# HDMI.net
KiCad netlist of a schematic drawn in Altium Designer
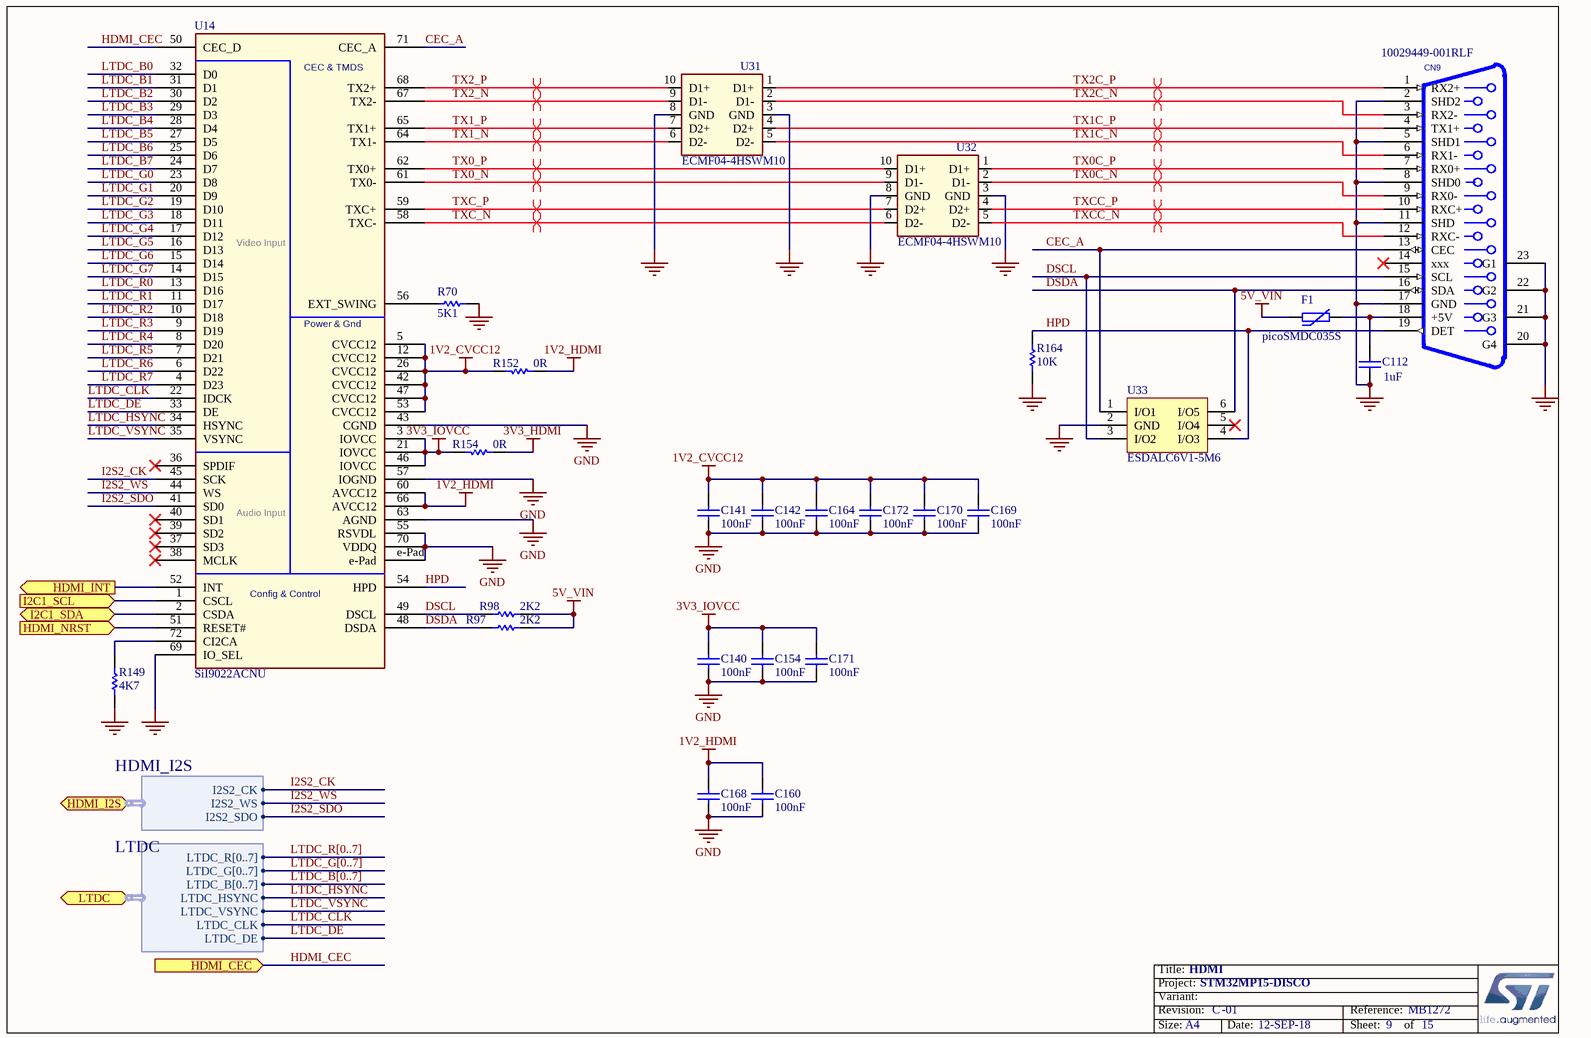
[diagram p0: HDMI.SchDoc]

(export (version "E")
  (design (tool "Eeschema 10.0.6"))
  (components
    (comp (ref "C112")
      (value "1uF")
      (footprint "C0402")
      (description "Capacitor,1uF,6V3,X5R,10%,0402")
      (fields
        (field (name "INTERNAL_PART_NUMBER") "MCD-00095")
        (field (name "MANUFACTURER_PART_NUMBER") "GRM155R61E105KA12")
        (field (name "PROVIDED_BY") "SUBCO")
      )
      (libsource (lib "MCD_PARTS_database") (part "Capacitor"))
    )
    (comp (ref "C140")
      (value "100nF")
      (footprint "C0402")
      (description "Capacitor,100nF,16V,X7R,10%,0402")
      (fields
        (field (name "INTERNAL_PART_NUMBER") "MCD-00006")
        (field (name "MANUFACTURER_PART_NUMBER") "CC0402KRX7R7BB104")
        (field (name "PROVIDED_BY") "SUBCO")
      )
      (libsource (lib "MCD_PARTS_database") (part "Capacitor"))
    )
    (comp (ref "C141")
      (value "100nF")
      (footprint "C0402")
      (description "Capacitor,100nF,16V,X7R,10%,0402")
      (fields
        (field (name "INTERNAL_PART_NUMBER") "MCD-00006")
        (field (name "MANUFACTURER_PART_NUMBER") "CC0402KRX7R7BB104")
        (field (name "PROVIDED_BY") "SUBCO")
      )
      (libsource (lib "MCD_PARTS_database") (part "Capacitor"))
    )
    (comp (ref "C142")
      (value "100nF")
      (footprint "C0402")
      (description "Capacitor,100nF,16V,X7R,10%,0402")
      (fields
        (field (name "INTERNAL_PART_NUMBER") "MCD-00006")
        (field (name "MANUFACTURER_PART_NUMBER") "CC0402KRX7R7BB104")
        (field (name "PROVIDED_BY") "SUBCO")
      )
      (libsource (lib "MCD_PARTS_database") (part "Capacitor"))
    )
    (comp (ref "C154")
      (value "100nF")
      (footprint "C0402")
      (description "Capacitor,100nF,16V,X7R,10%,0402")
      (fields
        (field (name "INTERNAL_PART_NUMBER") "MCD-00006")
        (field (name "MANUFACTURER_PART_NUMBER") "CC0402KRX7R7BB104")
        (field (name "PROVIDED_BY") "SUBCO")
      )
      (libsource (lib "MCD_PARTS_database") (part "Capacitor"))
    )
    (comp (ref "C160")
      (value "100nF")
      (footprint "C0402")
      (description "Capacitor,100nF,16V,X7R,10%,0402")
      (fields
        (field (name "INTERNAL_PART_NUMBER") "MCD-00006")
        (field (name "MANUFACTURER_PART_NUMBER") "CC0402KRX7R7BB104")
        (field (name "PROVIDED_BY") "SUBCO")
      )
      (libsource (lib "MCD_PARTS_database") (part "Capacitor"))
    )
    (comp (ref "C164")
      (value "100nF")
      (footprint "C0402")
      (description "Capacitor,100nF,16V,X7R,10%,0402")
      (fields
        (field (name "INTERNAL_PART_NUMBER") "MCD-00006")
        (field (name "MANUFACTURER_PART_NUMBER") "CC0402KRX7R7BB104")
        (field (name "PROVIDED_BY") "SUBCO")
      )
      (libsource (lib "MCD_PARTS_database") (part "Capacitor"))
    )
    (comp (ref "C168")
      (value "100nF")
      (footprint "C0402")
      (description "Capacitor,100nF,16V,X7R,10%,0402")
      (fields
        (field (name "INTERNAL_PART_NUMBER") "MCD-00006")
        (field (name "MANUFACTURER_PART_NUMBER") "CC0402KRX7R7BB104")
        (field (name "PROVIDED_BY") "SUBCO")
      )
      (libsource (lib "MCD_PARTS_database") (part "Capacitor"))
    )
    (comp (ref "C169")
      (value "100nF")
      (footprint "C0402")
      (description "Capacitor,100nF,16V,X7R,10%,0402")
      (fields
        (field (name "INTERNAL_PART_NUMBER") "MCD-00006")
        (field (name "MANUFACTURER_PART_NUMBER") "CC0402KRX7R7BB104")
        (field (name "PROVIDED_BY") "SUBCO")
      )
      (libsource (lib "MCD_PARTS_database") (part "Capacitor"))
    )
    (comp (ref "C170")
      (value "100nF")
      (footprint "C0402")
      (description "Capacitor,100nF,16V,X7R,10%,0402")
      (fields
        (field (name "INTERNAL_PART_NUMBER") "MCD-00006")
        (field (name "MANUFACTURER_PART_NUMBER") "CC0402KRX7R7BB104")
        (field (name "PROVIDED_BY") "SUBCO")
      )
      (libsource (lib "MCD_PARTS_database") (part "Capacitor"))
    )
    (comp (ref "C171")
      (value "100nF")
      (footprint "C0402")
      (description "Capacitor,100nF,16V,X7R,10%,0402")
      (fields
        (field (name "INTERNAL_PART_NUMBER") "MCD-00006")
        (field (name "MANUFACTURER_PART_NUMBER") "CC0402KRX7R7BB104")
        (field (name "PROVIDED_BY") "SUBCO")
      )
      (libsource (lib "MCD_PARTS_database") (part "Capacitor"))
    )
    (comp (ref "C172")
      (value "100nF")
      (footprint "C0402")
      (description "Capacitor,100nF,16V,X7R,10%,0402")
      (fields
        (field (name "INTERNAL_PART_NUMBER") "MCD-00006")
        (field (name "MANUFACTURER_PART_NUMBER") "CC0402KRX7R7BB104")
        (field (name "PROVIDED_BY") "SUBCO")
      )
      (libsource (lib "MCD_PARTS_database") (part "Capacitor"))
    )
    (comp (ref "CN9")
      (value "10029449-001RLF")
      (footprint "CON_HDMI_FCI-AMPHENOL_10029449-001RLF")
      (description "HDMI Receptacle Type A 19pins standard Connector")
      (fields
        (field (name "INTERNAL_PART_NUMBER") "MCD-00307")
        (field (name "MANUFACTURER") "FCI")
        (field (name "PROVIDED_BY") "SUBCO")
      )
      (libsource (lib "MCD_PARTS_database") (part "HDMI_TypeA_DB19_7"))
    )
    (comp (ref "F1")
      (value "picoSMDC035S")
      (footprint "R0805")
      (description "Surface mount resettable polyswitch fuse.I hold=0.35A and I trigger=0.75A")
      (fields
        (field (name "INTERNAL_PART_NUMBER") "MCD-01133")
        (field (name "MANUFACTURER") "TE CONNECTIVITY")
        (field (name "PROVIDED_BY") "SUBCO")
      )
      (libsource (lib "MCD_PARTS_database") (part "picoSMDC035S"))
    )
    (comp (ref "R70")
      (value "5K1")
      (footprint "R0402")
      (description "Resistor,5K1,0402,1%,1/16W")
      (fields
        (field (name "INTERNAL_PART_NUMBER") "MCD-00333")
        (field (name "MANUFACTURER_PART_NUMBER") "RC0402FR-075K1L")
        (field (name "PROVIDED_BY") "SUBCO")
      )
      (libsource (lib "MCD_PARTS_database") (part "Resistor"))
    )
    (comp (ref "R97")
      (value "2K2")
      (footprint "R0402")
      (description "Resistor,2K2,0402,1%,1/16W")
      (fields
        (field (name "INTERNAL_PART_NUMBER") "MCD-00057")
        (field (name "MANUFACTURER_PART_NUMBER") "RC0402FR-072K2L")
        (field (name "PROVIDED_BY") "SUBCO")
      )
      (libsource (lib "MCD_PARTS_database") (part "Resistor"))
    )
    (comp (ref "R98")
      (value "2K2")
      (footprint "R0402")
      (description "Resistor,2K2,0402,1%,1/16W")
      (fields
        (field (name "INTERNAL_PART_NUMBER") "MCD-00057")
        (field (name "MANUFACTURER_PART_NUMBER") "RC0402FR-072K2L")
        (field (name "PROVIDED_BY") "SUBCO")
      )
      (libsource (lib "MCD_PARTS_database") (part "Resistor"))
    )
    (comp (ref "R149")
      (value "4K7")
      (footprint "R0402")
      (description "Resistor,4K7,0402,1%,1/16W")
      (fields
        (field (name "INTERNAL_PART_NUMBER") "MCD-00065")
        (field (name "MANUFACTURER_PART_NUMBER") "RC0402FR-074K7L")
        (field (name "PROVIDED_BY") "SUBCO")
      )
      (libsource (lib "MCD_PARTS_database") (part "Resistor"))
    )
    (comp (ref "R152")
      (value "0R")
      (footprint "R0402")
      (description "Resistor,0R,0402,5%,1/16W")
      (fields
        (field (name "INTERNAL_PART_NUMBER") "MCD-00052")
        (field (name "MANUFACTURER_PART_NUMBER") "RC0402JR-070RL")
        (field (name "PROVIDED_BY") "SUBCO")
      )
      (libsource (lib "MCD_PARTS_database") (part "Resistor"))
    )
    (comp (ref "R154")
      (value "0R")
      (footprint "R0402")
      (description "Resistor,0R,0402,5%,1/16W")
      (fields
        (field (name "INTERNAL_PART_NUMBER") "MCD-00052")
        (field (name "MANUFACTURER_PART_NUMBER") "RC0402JR-070RL")
        (field (name "PROVIDED_BY") "SUBCO")
      )
      (libsource (lib "MCD_PARTS_database") (part "Resistor"))
    )
    (comp (ref "R164")
      (value "10K")
      (footprint "R0402")
      (description "Resistor,10K,0402,1%,1/16W")
      (fields
        (field (name "INTERNAL_PART_NUMBER") "MCD-00053")
        (field (name "MANUFACTURER_PART_NUMBER") "RC0402FR-0710KL")
        (field (name "PROVIDED_BY") "SUBCO")
      )
      (libsource (lib "MCD_PARTS_database") (part "Resistor"))
    )
    (comp (ref "U14")
      (value "SiI9022ACNU")
      (footprint "ICC_QFN72-EPAD_10X10_P050")
      (description "HDMI Transmitter, 72-pin 10 × 10 mm QFN")
      (fields
        (field (name "INTERNAL_PART_NUMBER") "MCD-00267")
        (field (name "MANUFACTURER") "LATTICE")
        (field (name "PROVIDED_BY") "SUBCO")
      )
      (libsource (lib "MCD_PARTS_database") (part "SiI9022ACNU"))
    )
    (comp (ref "U31")
      (value "ECMF04-4HSWM10")
      (footprint "ESD_UQFN-10L_2P60X1P35_P050")
      (description "ESD protection & Common Filter High Speed serial Interfaces")
      (fields
        (field (name "INTERNAL_PART_NUMBER") "MCD-00297")
        (field (name "MANUFACTURER") "STMICROELECTRONICS")
        (field (name "PROVIDED_BY") "SUBCO with ST control")
      )
      (libsource (lib "MCD_PARTS_database") (part "ECMF04-4HSWM10"))
    )
    (comp (ref "U32")
      (value "ECMF04-4HSWM10")
      (footprint "ESD_UQFN-10L_2P60X1P35_P050")
      (description "ESD protection & Common Filter High Speed serial Interfaces")
      (fields
        (field (name "INTERNAL_PART_NUMBER") "MCD-00297")
        (field (name "MANUFACTURER") "STMICROELECTRONICS")
        (field (name "PROVIDED_BY") "SUBCO with ST control")
      )
      (libsource (lib "MCD_PARTS_database") (part "ECMF04-4HSWM10"))
    )
    (comp (ref "U33")
      (value "ESDALC6V1-5M6")
      (footprint "ESD_UQFN-6L_1P45X1_P050")
      (description "ESD protection , 5 lines")
      (fields
        (field (name "INTERNAL_PART_NUMBER") "MCD-01457")
        (field (name "MANUFACTURER") "STMICROELECTRONICS")
        (field (name "PROVIDED_BY") "SUBCO")
      )
      (libsource (lib "MCD_PARTS_database") (part "ESDALC6V1-5M6"))
    )
  )
  (nets
    (net (code "3") (name "/CEC_A") (class "Default")
      (node (ref "CN9") (pin "13") (pinfunction "CEC_13") (pintype "bidirectional"))
      (node (ref "U14") (pin "71") (pinfunction "CEC_A_71") (pintype "passive"))
      (node (ref "U33") (pin "1") (pinfunction "I/O1_1") (pintype "passive"))
    )
    (net (code "4") (name "/DSCL") (class "Default")
      (node (ref "CN9") (pin "15") (pinfunction "SCL_15") (pintype "input"))
      (node (ref "R98") (pin "1") (pinfunction "1_1") (pintype "passive"))
      (node (ref "U14") (pin "49") (pinfunction "DSCL_49") (pintype "passive"))
      (node (ref "U33") (pin "3") (pinfunction "I/O2_3") (pintype "passive"))
    )
    (net (code "5") (name "/DSDA") (class "Default")
      (node (ref "CN9") (pin "16") (pinfunction "SDA_16") (pintype "bidirectional"))
      (node (ref "R97") (pin "1") (pinfunction "1_1") (pintype "passive"))
      (node (ref "U14") (pin "48") (pinfunction "DSDA_48") (pintype "passive"))
      (node (ref "U33") (pin "6") (pinfunction "I/O5_6") (pintype "passive"))
    )
    (net (code "6") (name "/HDMI_CEC") (class "Default")
      (node (ref "U14") (pin "50") (pinfunction "CEC_D_50") (pintype "passive"))
    )
    (net (code "7") (name "/HDMI_INT") (class "Default")
      (node (ref "U14") (pin "52") (pinfunction "INT_52") (pintype "passive"))
    )
    (net (code "8") (name "/HDMI_NRST") (class "Default")
      (node (ref "U14") (pin "51") (pinfunction "RESET#_51") (pintype "passive"))
    )
    (net (code "9") (name "/HPD") (class "Default")
      (node (ref "CN9") (pin "19") (pinfunction "DET_19") (pintype "output"))
      (node (ref "R164") (pin "2") (pinfunction "2_2") (pintype "passive"))
      (node (ref "U14") (pin "54") (pinfunction "HPD_54") (pintype "passive"))
      (node (ref "U33") (pin "4") (pinfunction "I/O3_4") (pintype "passive"))
    )
    (net (code "10") (name "/I2C1_SCL") (class "Default")
      (node (ref "U14") (pin "1") (pinfunction "CSCL_1") (pintype "passive"))
    )
    (net (code "11") (name "/I2C1_SDA") (class "Default")
      (node (ref "U14") (pin "2") (pinfunction "CSDA_2") (pintype "passive"))
    )
    (net (code "12") (name "/I2S2_CK") (class "Default")
      (node (ref "U14") (pin "45") (pinfunction "SCK_45") (pintype "passive"))
    )
    (net (code "13") (name "/I2S2_SDO") (class "Default")
      (node (ref "U14") (pin "41") (pinfunction "SD0_41") (pintype "passive"))
    )
    (net (code "14") (name "/I2S2_WS") (class "Default")
      (node (ref "U14") (pin "44") (pinfunction "WS_44") (pintype "passive"))
    )
    (net (code "15") (name "/LTDC_B0") (class "Default")
      (node (ref "U14") (pin "32") (pinfunction "D0_32") (pintype "passive"))
    )
    (net (code "16") (name "/LTDC_B1") (class "Default")
      (node (ref "U14") (pin "31") (pinfunction "D1_31") (pintype "passive"))
    )
    (net (code "17") (name "/LTDC_B2") (class "Default")
      (node (ref "U14") (pin "30") (pinfunction "D2_30") (pintype "passive"))
    )
    (net (code "18") (name "/LTDC_B3") (class "Default")
      (node (ref "U14") (pin "29") (pinfunction "D3_29") (pintype "passive"))
    )
    (net (code "19") (name "/LTDC_B4") (class "Default")
      (node (ref "U14") (pin "28") (pinfunction "D4_28") (pintype "passive"))
    )
    (net (code "20") (name "/LTDC_B5") (class "Default")
      (node (ref "U14") (pin "27") (pinfunction "D5_27") (pintype "passive"))
    )
    (net (code "21") (name "/LTDC_B6") (class "Default")
      (node (ref "U14") (pin "25") (pinfunction "D6_25") (pintype "passive"))
    )
    (net (code "22") (name "/LTDC_B7") (class "Default")
      (node (ref "U14") (pin "24") (pinfunction "D7_24") (pintype "passive"))
    )
    (net (code "24") (name "/LTDC_CLK") (class "Default")
      (node (ref "U14") (pin "22") (pinfunction "IDCK_22") (pintype "passive"))
    )
    (net (code "25") (name "/LTDC_DE") (class "Default")
      (node (ref "U14") (pin "33") (pinfunction "DE_33") (pintype "passive"))
    )
    (net (code "26") (name "/LTDC_G0") (class "Default")
      (node (ref "U14") (pin "23") (pinfunction "D8_23") (pintype "passive"))
    )
    (net (code "27") (name "/LTDC_G1") (class "Default")
      (node (ref "U14") (pin "20") (pinfunction "D9_20") (pintype "passive"))
    )
    (net (code "28") (name "/LTDC_G2") (class "Default")
      (node (ref "U14") (pin "19") (pinfunction "D10_19") (pintype "passive"))
    )
    (net (code "29") (name "/LTDC_G3") (class "Default")
      (node (ref "U14") (pin "18") (pinfunction "D11_18") (pintype "passive"))
    )
    (net (code "30") (name "/LTDC_G4") (class "Default")
      (node (ref "U14") (pin "17") (pinfunction "D12_17") (pintype "passive"))
    )
    (net (code "31") (name "/LTDC_G5") (class "Default")
      (node (ref "U14") (pin "16") (pinfunction "D13_16") (pintype "passive"))
    )
    (net (code "32") (name "/LTDC_G6") (class "Default")
      (node (ref "U14") (pin "15") (pinfunction "D14_15") (pintype "passive"))
    )
    (net (code "33") (name "/LTDC_G7") (class "Default")
      (node (ref "U14") (pin "14") (pinfunction "D15_14") (pintype "passive"))
    )
    (net (code "35") (name "/LTDC_HSYNC") (class "Default")
      (node (ref "U14") (pin "34") (pinfunction "HSYNC_34") (pintype "passive"))
    )
    (net (code "36") (name "/LTDC_R0") (class "Default")
      (node (ref "U14") (pin "13") (pinfunction "D16_13") (pintype "passive"))
    )
    (net (code "37") (name "/LTDC_R1") (class "Default")
      (node (ref "U14") (pin "11") (pinfunction "D17_11") (pintype "passive"))
    )
    (net (code "38") (name "/LTDC_R2") (class "Default")
      (node (ref "U14") (pin "10") (pinfunction "D18_10") (pintype "passive"))
    )
    (net (code "39") (name "/LTDC_R3") (class "Default")
      (node (ref "U14") (pin "9") (pinfunction "D19_9") (pintype "passive"))
    )
    (net (code "40") (name "/LTDC_R4") (class "Default")
      (node (ref "U14") (pin "8") (pinfunction "D20_8") (pintype "passive"))
    )
    (net (code "41") (name "/LTDC_R5") (class "Default")
      (node (ref "U14") (pin "7") (pinfunction "D21_7") (pintype "passive"))
    )
    (net (code "42") (name "/LTDC_R6") (class "Default")
      (node (ref "U14") (pin "6") (pinfunction "D22_6") (pintype "passive"))
    )
    (net (code "43") (name "/LTDC_R7") (class "Default")
      (node (ref "U14") (pin "4") (pinfunction "D23_4") (pintype "passive"))
    )
    (net (code "45") (name "/LTDC_VSYNC") (class "Default")
      (node (ref "U14") (pin "35") (pinfunction "VSYNC_35") (pintype "passive"))
    )
    (net (code "46") (name "/TX0C_N") (class "Default")
      (node (ref "CN9") (pin "9") (pinfunction "RX0-_9") (pintype "input"))
      (node (ref "U32") (pin "2") (pinfunction "D1-_2") (pintype "passive"))
    )
    (net (code "47") (name "/TX0C_P") (class "Default")
      (node (ref "CN9") (pin "7") (pinfunction "RX0+_7") (pintype "input"))
      (node (ref "U32") (pin "1") (pinfunction "D1+_1") (pintype "passive"))
    )
    (net (code "48") (name "/TX0_N") (class "Default")
      (node (ref "U14") (pin "61") (pinfunction "TX0-_61") (pintype "passive"))
      (node (ref "U32") (pin "9") (pinfunction "D1-_9") (pintype "passive"))
    )
    (net (code "49") (name "/TX0_P") (class "Default")
      (node (ref "U14") (pin "62") (pinfunction "TX0+_62") (pintype "passive"))
      (node (ref "U32") (pin "10") (pinfunction "D1+_10") (pintype "passive"))
    )
    (net (code "50") (name "/TX1C_N") (class "Default")
      (node (ref "CN9") (pin "6") (pinfunction "RX1-_6") (pintype "input"))
      (node (ref "U31") (pin "5") (pinfunction "D2-_5") (pintype "open_collector"))
    )
    (net (code "51") (name "/TX1C_P") (class "Default")
      (node (ref "CN9") (pin "4") (pinfunction "TX1+_4") (pintype "input"))
      (node (ref "U31") (pin "4") (pinfunction "D2+_4") (pintype "open_collector"))
    )
    (net (code "52") (name "/TX1_N") (class "Default")
      (node (ref "U14") (pin "64") (pinfunction "TX1-_64") (pintype "passive"))
      (node (ref "U31") (pin "6") (pinfunction "D2-_6") (pintype "passive"))
    )
    (net (code "53") (name "/TX1_P") (class "Default")
      (node (ref "U14") (pin "65") (pinfunction "TX1+_65") (pintype "passive"))
      (node (ref "U31") (pin "7") (pinfunction "D2+_7") (pintype "passive"))
    )
    (net (code "54") (name "/TX2C_N") (class "Default")
      (node (ref "CN9") (pin "3") (pinfunction "RX2-_3") (pintype "input"))
      (node (ref "U31") (pin "2") (pinfunction "D1-_2") (pintype "passive"))
    )
    (net (code "55") (name "/TX2C_P") (class "Default")
      (node (ref "CN9") (pin "1") (pinfunction "RX2+_1") (pintype "input"))
      (node (ref "U31") (pin "1") (pinfunction "D1+_1") (pintype "passive"))
    )
    (net (code "56") (name "/TX2_N") (class "Default")
      (node (ref "U14") (pin "67") (pinfunction "TX2-_67") (pintype "passive"))
      (node (ref "U31") (pin "9") (pinfunction "D1-_9") (pintype "passive"))
    )
    (net (code "57") (name "/TX2_P") (class "Default")
      (node (ref "U14") (pin "68") (pinfunction "TX2+_68") (pintype "passive"))
      (node (ref "U31") (pin "10") (pinfunction "D1+_10") (pintype "passive"))
    )
    (net (code "58") (name "/TXCC_N") (class "Default")
      (node (ref "CN9") (pin "12") (pinfunction "RXC-_12") (pintype "input"))
      (node (ref "U32") (pin "5") (pinfunction "D2-_5") (pintype "open_collector"))
    )
    (net (code "59") (name "/TXCC_P") (class "Default")
      (node (ref "CN9") (pin "10") (pinfunction "RXC+_10") (pintype "input"))
      (node (ref "U32") (pin "4") (pinfunction "D2+_4") (pintype "open_collector"))
    )
    (net (code "60") (name "/TXC_N") (class "Default")
      (node (ref "U14") (pin "58") (pinfunction "TXC-_58") (pintype "passive"))
      (node (ref "U32") (pin "6") (pinfunction "D2-_6") (pintype "passive"))
    )
    (net (code "61") (name "/TXC_P") (class "Default")
      (node (ref "U14") (pin "59") (pinfunction "TXC+_59") (pintype "passive"))
      (node (ref "U32") (pin "7") (pinfunction "D2+_7") (pintype "passive"))
    )
    (net (code "64") (name "1V2_CVCC12") (class "Default")
      (node (ref "C141") (pin "2") (pinfunction "2_2") (pintype "passive"))
      (node (ref "C142") (pin "2") (pinfunction "2_2") (pintype "passive"))
      (node (ref "C164") (pin "2") (pinfunction "2_2") (pintype "passive"))
      (node (ref "C169") (pin "2") (pinfunction "2_2") (pintype "passive"))
      (node (ref "C170") (pin "2") (pinfunction "2_2") (pintype "passive"))
      (node (ref "C172") (pin "2") (pinfunction "2_2") (pintype "passive"))
      (node (ref "R152") (pin "1") (pinfunction "1_1") (pintype "passive"))
      (node (ref "U14") (pin "12") (pinfunction "CVCC12_12") (pintype "power_in"))
      (node (ref "U14") (pin "26") (pinfunction "CVCC12_26") (pintype "power_in"))
      (node (ref "U14") (pin "42") (pinfunction "CVCC12_42") (pintype "power_in"))
      (node (ref "U14") (pin "47") (pinfunction "CVCC12_47") (pintype "power_in"))
      (node (ref "U14") (pin "5") (pinfunction "CVCC12_5") (pintype "power_in"))
      (node (ref "U14") (pin "53") (pinfunction "CVCC12_53") (pintype "power_in"))
    )
    (net (code "65") (name "1V2_HDMI") (class "Default")
      (node (ref "C160") (pin "2") (pinfunction "2_2") (pintype "passive"))
      (node (ref "C168") (pin "2") (pinfunction "2_2") (pintype "passive"))
      (node (ref "R152") (pin "2") (pinfunction "2_2") (pintype "passive"))
      (node (ref "U14") (pin "60") (pinfunction "AVCC12_60") (pintype "power_in"))
      (node (ref "U14") (pin "66") (pinfunction "AVCC12_66") (pintype "power_in"))
    )
    (net (code "66") (name "3V3_HDMI") (class "Default")
      (node (ref "R154") (pin "2") (pinfunction "2_2") (pintype "passive"))
    )
    (net (code "67") (name "3V3_IOVCC") (class "Default")
      (node (ref "C140") (pin "2") (pinfunction "2_2") (pintype "passive"))
      (node (ref "C154") (pin "2") (pinfunction "2_2") (pintype "passive"))
      (node (ref "C171") (pin "2") (pinfunction "2_2") (pintype "passive"))
      (node (ref "R154") (pin "1") (pinfunction "1_1") (pintype "passive"))
      (node (ref "U14") (pin "21") (pinfunction "IOVCC_21") (pintype "power_in"))
      (node (ref "U14") (pin "3") (pinfunction "IOVCC_3") (pintype "power_in"))
      (node (ref "U14") (pin "46") (pinfunction "IOVCC_46") (pintype "power_in"))
    )
    (net (code "68") (name "5V_VIN") (class "Default")
      (node (ref "F1") (pin "1") (pinfunction "1_1") (pintype "passive"))
      (node (ref "R97") (pin "2") (pinfunction "2_2") (pintype "passive"))
      (node (ref "R98") (pin "2") (pinfunction "2_2") (pintype "passive"))
    )
    (net (code "69") (name "GND") (class "Default")
      (node (ref "C112") (pin "1") (pinfunction "1_1") (pintype "passive"))
      (node (ref "C140") (pin "1") (pinfunction "1_1") (pintype "passive"))
      (node (ref "C141") (pin "1") (pinfunction "1_1") (pintype "passive"))
      (node (ref "C142") (pin "1") (pinfunction "1_1") (pintype "passive"))
      (node (ref "C154") (pin "1") (pinfunction "1_1") (pintype "passive"))
      (node (ref "C160") (pin "1") (pinfunction "1_1") (pintype "passive"))
      (node (ref "C164") (pin "1") (pinfunction "1_1") (pintype "passive"))
      (node (ref "C168") (pin "1") (pinfunction "1_1") (pintype "passive"))
      (node (ref "C169") (pin "1") (pinfunction "1_1") (pintype "passive"))
      (node (ref "C170") (pin "1") (pinfunction "1_1") (pintype "passive"))
      (node (ref "C171") (pin "1") (pinfunction "1_1") (pintype "passive"))
      (node (ref "C172") (pin "1") (pinfunction "1_1") (pintype "passive"))
      (node (ref "CN9") (pin "11") (pinfunction "SHD_11") (pintype "passive"))
      (node (ref "CN9") (pin "17") (pinfunction "GND_17") (pintype "passive"))
      (node (ref "CN9") (pin "2") (pinfunction "SHD2_2") (pintype "passive"))
      (node (ref "CN9") (pin "20") (pinfunction "G4_20") (pintype "passive"))
      (node (ref "CN9") (pin "21") (pinfunction "G3_21") (pintype "passive"))
      (node (ref "CN9") (pin "22") (pinfunction "G2_22") (pintype "passive"))
      (node (ref "CN9") (pin "23") (pinfunction "G1_23") (pintype "passive"))
      (node (ref "CN9") (pin "5") (pinfunction "SHD1_5") (pintype "passive"))
      (node (ref "CN9") (pin "8") (pinfunction "SHD0_8") (pintype "passive"))
      (node (ref "R149") (pin "1") (pinfunction "1_1") (pintype "passive"))
      (node (ref "R164") (pin "1") (pinfunction "1_1") (pintype "passive"))
      (node (ref "R70") (pin "2") (pinfunction "2_2") (pintype "passive"))
      (node (ref "U14") (pin "43") (pinfunction "CGND_43") (pintype "power_in"))
      (node (ref "U14") (pin "55") (pinfunction "RSVDL_55") (pintype "power_in"))
      (node (ref "U14") (pin "57") (pinfunction "IOGND_57") (pintype "power_in"))
      (node (ref "U14") (pin "63") (pinfunction "AGND_63") (pintype "power_in"))
      (node (ref "U14") (pin "69") (pinfunction "IO_SEL_69") (pintype "passive"))
      (node (ref "U14") (pin "70") (pinfunction "VDDQ_70") (pintype "power_in"))
      (node (ref "U14") (pin "e-Pad") (pinfunction "e-Pad_e-Pad") (pintype "power_in"))
      (node (ref "U31") (pin "3") (pinfunction "GND_3") (pintype "power_in"))
      (node (ref "U31") (pin "8") (pinfunction "GND_8") (pintype "power_in"))
      (node (ref "U32") (pin "3") (pinfunction "GND_3") (pintype "power_in"))
      (node (ref "U32") (pin "8") (pinfunction "GND_8") (pintype "power_in"))
      (node (ref "U33") (pin "2") (pinfunction "GND_2") (pintype "passive"))
    )
    (net (code "70") (name "Net-(CN9-+5V)") (class "Default")
      (node (ref "C112") (pin "2") (pinfunction "2_2") (pintype "passive"))
      (node (ref "CN9") (pin "18") (pinfunction "+5V_18") (pintype "power_in"))
      (node (ref "F1") (pin "2") (pinfunction "2_2") (pintype "passive"))
    )
    (net (code "71") (name "Net-(U14-CI2CA)") (class "Default")
      (node (ref "R149") (pin "2") (pinfunction "2_2") (pintype "passive"))
      (node (ref "U14") (pin "72") (pinfunction "CI2CA_72") (pintype "passive"))
    )
    (net (code "72") (name "Net-(U14-EXT_SWING)") (class "Default")
      (node (ref "R70") (pin "1") (pinfunction "1_1") (pintype "passive"))
      (node (ref "U14") (pin "56") (pinfunction "EXT_SWING_56") (pintype "passive"))
    )
    (net (code "73") (name "unconnected-(CN9-xxx-Pad14)") (class "Default")
      (node (ref "CN9") (pin "14") (pinfunction "xxx_14") (pintype "passive+no_connect"))
    )
    (net (code "74") (name "unconnected-(U14-MCLK-Pad38)") (class "Default")
      (node (ref "U14") (pin "38") (pinfunction "MCLK_38") (pintype "passive+no_connect"))
    )
    (net (code "75") (name "unconnected-(U14-SD1-Pad40)") (class "Default")
      (node (ref "U14") (pin "40") (pinfunction "SD1_40") (pintype "passive+no_connect"))
    )
    (net (code "76") (name "unconnected-(U14-SD2-Pad39)") (class "Default")
      (node (ref "U14") (pin "39") (pinfunction "SD2_39") (pintype "passive+no_connect"))
    )
    (net (code "77") (name "unconnected-(U14-SD3-Pad37)") (class "Default")
      (node (ref "U14") (pin "37") (pinfunction "SD3_37") (pintype "passive+no_connect"))
    )
    (net (code "78") (name "unconnected-(U14-SPDIF-Pad36)") (class "Default")
      (node (ref "U14") (pin "36") (pinfunction "SPDIF_36") (pintype "passive+no_connect"))
    )
    (net (code "79") (name "unconnected-(U33-I{slash}O4-Pad5)") (class "Default")
      (node (ref "U33") (pin "5") (pinfunction "I/O4_5") (pintype "passive+no_connect"))
    )
  )
)
